# V1_0.net
KiCad netlist of a schematic drawn in Altium Designer
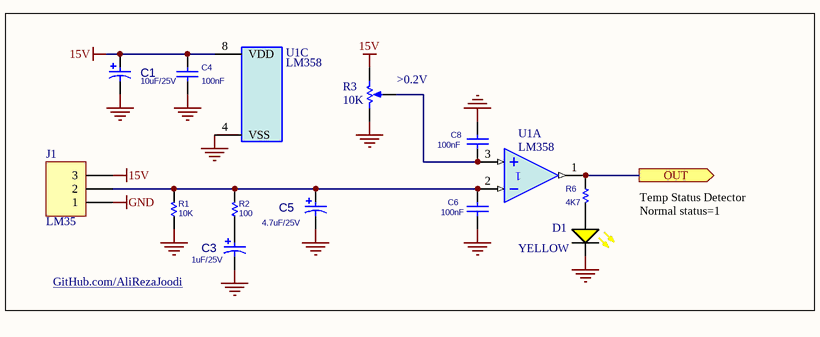
[diagram p0: V1.0.SchDoc]

(export (version "E")
  (design (tool "Eeschema 10.0.6"))
  (components
    (comp (ref "C1")
      (value "10uF/25V")
      (footprint "C_THD_EL_(P2.54-D6-H11)")
      (description "Capacitor, Electrolytic")
      (libsource (lib "Passive") (part "Capacitor_Electrolytic"))
    )
    (comp (ref "C3")
      (value "1uF/25V")
      (footprint "C_THD_EL_(P2.54-D6-H11)")
      (description "Capacitor, Electrolytic")
      (libsource (lib "Passive") (part "Capacitor_Electrolytic"))
    )
    (comp (ref "C4")
      (value "100nF")
      (footprint "C_THD_CER_(P2.54-D3.5-T1.5)")
      (description "Capacitor, Ceramic Multilayer")
      (libsource (lib "Passive") (part "Capacitor_Ceramic"))
    )
    (comp (ref "C5")
      (value "4.7uF/25V")
      (footprint "C_THD_EL_(P2.54-D6-H11)")
      (description "Capacitor, Electrolytic")
      (libsource (lib "Passive") (part "Capacitor_Electrolytic"))
    )
    (comp (ref "C6")
      (value "100nF")
      (footprint "C_THD_CER_(P2.54-D3.5-T1.5)")
      (description "Capacitor, Ceramic Multilayer")
      (libsource (lib "Passive") (part "Capacitor_Ceramic"))
    )
    (comp (ref "C8")
      (value "100nF")
      (footprint "C_THD_CER_(P2.54-D3.5-T1.5)")
      (description "Capacitor, Ceramic Multilayer")
      (libsource (lib "Passive") (part "Capacitor_Ceramic"))
    )
    (comp (ref "D1")
      (value "YELLOW")
      (footprint "LED_THD_5MM_YELLOW")
      (description "LED, Yellow")
      (fields (field (name "MANUFACTURER") "Generic Components") (field (name "PUBLISHER") "Altium Limited"))
      (libsource (lib "Display") (part "LED_YELLOW"))
    )
    (comp (ref "J1")
      (value "3PIN")
      (footprint "Connector_Phoenix_3PIN_MSTB")
      (description "Header, 3-Pin")
      (fields (field (name "MANUFACTURER") "Generic Components") (field (name "PUBLISHER") "Altium Limited"))
      (libsource (lib "Miscellaneous Connectors") (part "Header 3"))
    )
    (comp (ref "R1")
      (value "10K")
      (footprint "R_THD_AXIAL0.4(1/4W)")
      (description "Resistor,")
      (libsource (lib "Passive") (part "Resistor"))
    )
    (comp (ref "R2")
      (value "100")
      (footprint "R_THD_AXIAL0.4(1/4W)")
      (description "Resistor,")
      (libsource (lib "Passive") (part "Resistor"))
    )
    (comp (ref "R3")
      (value "10K")
      (footprint "POT_THD_3296W")
      (description "Potentiometer")
      (libsource (lib "Passive") (part "Resistor_Pot"))
    )
    (comp (ref "R6")
      (value "4K7")
      (footprint "R_THD_AXIAL0.4(1/4W)")
      (description "Resistor,")
      (libsource (lib "Passive") (part "Resistor"))
    )
    (comp (ref "U1")
      (value "LM358")
      (footprint "751-02_L")
      (description "Dual Low-Power Operational Amplifier")
      (fields (field (name "PUBLISHER") "Altium Limited"))
      (libsource (lib "Op-Amp") (part "LM358"))
    )
  )
  (nets
    (net (code "1") (name "/OUT") (class "Default")
      (node (ref "R6") (pin "2") (pinfunction "2_2") (pintype "passive"))
      (node (ref "U1") (pin "1") (pinfunction "OUT_1") (pintype "output"))
    )
    (net (code "2") (name "15V") (class "Default")
      (node (ref "C1") (pin "1") (pinfunction "1_1") (pintype "passive"))
      (node (ref "C4") (pin "1") (pinfunction "1_1") (pintype "passive"))
      (node (ref "J1") (pin "3") (pinfunction "3_3") (pintype "passive"))
      (node (ref "R3") (pin "1") (pinfunction "TOP_1") (pintype "passive"))
      (node (ref "U1") (pin "8") (pinfunction "VDD_8") (pintype "passive"))
    )
    (net (code "3") (name "GND") (class "Default")
      (node (ref "C1") (pin "2") (pinfunction "2_2") (pintype "passive"))
      (node (ref "C3") (pin "2") (pinfunction "2_2") (pintype "passive"))
      (node (ref "C4") (pin "2") (pinfunction "2_2") (pintype "passive"))
      (node (ref "C5") (pin "2") (pinfunction "2_2") (pintype "passive"))
      (node (ref "C6") (pin "2") (pinfunction "2_2") (pintype "passive"))
      (node (ref "C8") (pin "2") (pinfunction "2_2") (pintype "passive"))
      (node (ref "D1") (pin "2") (pinfunction "K_2") (pintype "passive"))
      (node (ref "J1") (pin "1") (pinfunction "1_1") (pintype "passive"))
      (node (ref "R1") (pin "2") (pinfunction "2_2") (pintype "passive"))
      (node (ref "R3") (pin "3") (pinfunction "BOT_3") (pintype "passive"))
      (node (ref "U1") (pin "4") (pinfunction "VSS_4") (pintype "power_in"))
    )
    (net (code "4") (name "Net-(C3-Pad1)") (class "Default")
      (node (ref "C3") (pin "1") (pinfunction "1_1") (pintype "passive"))
      (node (ref "R2") (pin "2") (pinfunction "2_2") (pintype "passive"))
    )
    (net (code "5") (name "Net-(D1-A)") (class "Default")
      (node (ref "D1") (pin "1") (pinfunction "A_1") (pintype "passive"))
      (node (ref "R6") (pin "1") (pinfunction "1_1") (pintype "passive"))
    )
    (net (code "6") (name "Net-(R3-TAP)") (class "Default")
      (node (ref "C8") (pin "1") (pinfunction "1_1") (pintype "passive"))
      (node (ref "R3") (pin "2") (pinfunction "TAP_2") (pintype "passive"))
      (node (ref "U1") (pin "3") (pinfunction "IN+_3") (pintype "input"))
    )
    (net (code "7") (name "Net-(U1A-IN-)") (class "Default")
      (node (ref "C5") (pin "1") (pinfunction "1_1") (pintype "passive"))
      (node (ref "C6") (pin "1") (pinfunction "1_1") (pintype "passive"))
      (node (ref "J1") (pin "2") (pinfunction "2_2") (pintype "passive"))
      (node (ref "R1") (pin "1") (pinfunction "1_1") (pintype "passive"))
      (node (ref "R2") (pin "1") (pinfunction "1_1") (pintype "passive"))
      (node (ref "U1") (pin "2") (pinfunction "IN-_2") (pintype "input"))
    )
  )
)
